# SCH_t4_MFA_LCD_2021-12-15.net
KiCad netlist of a schematic drawn in EasyEDA
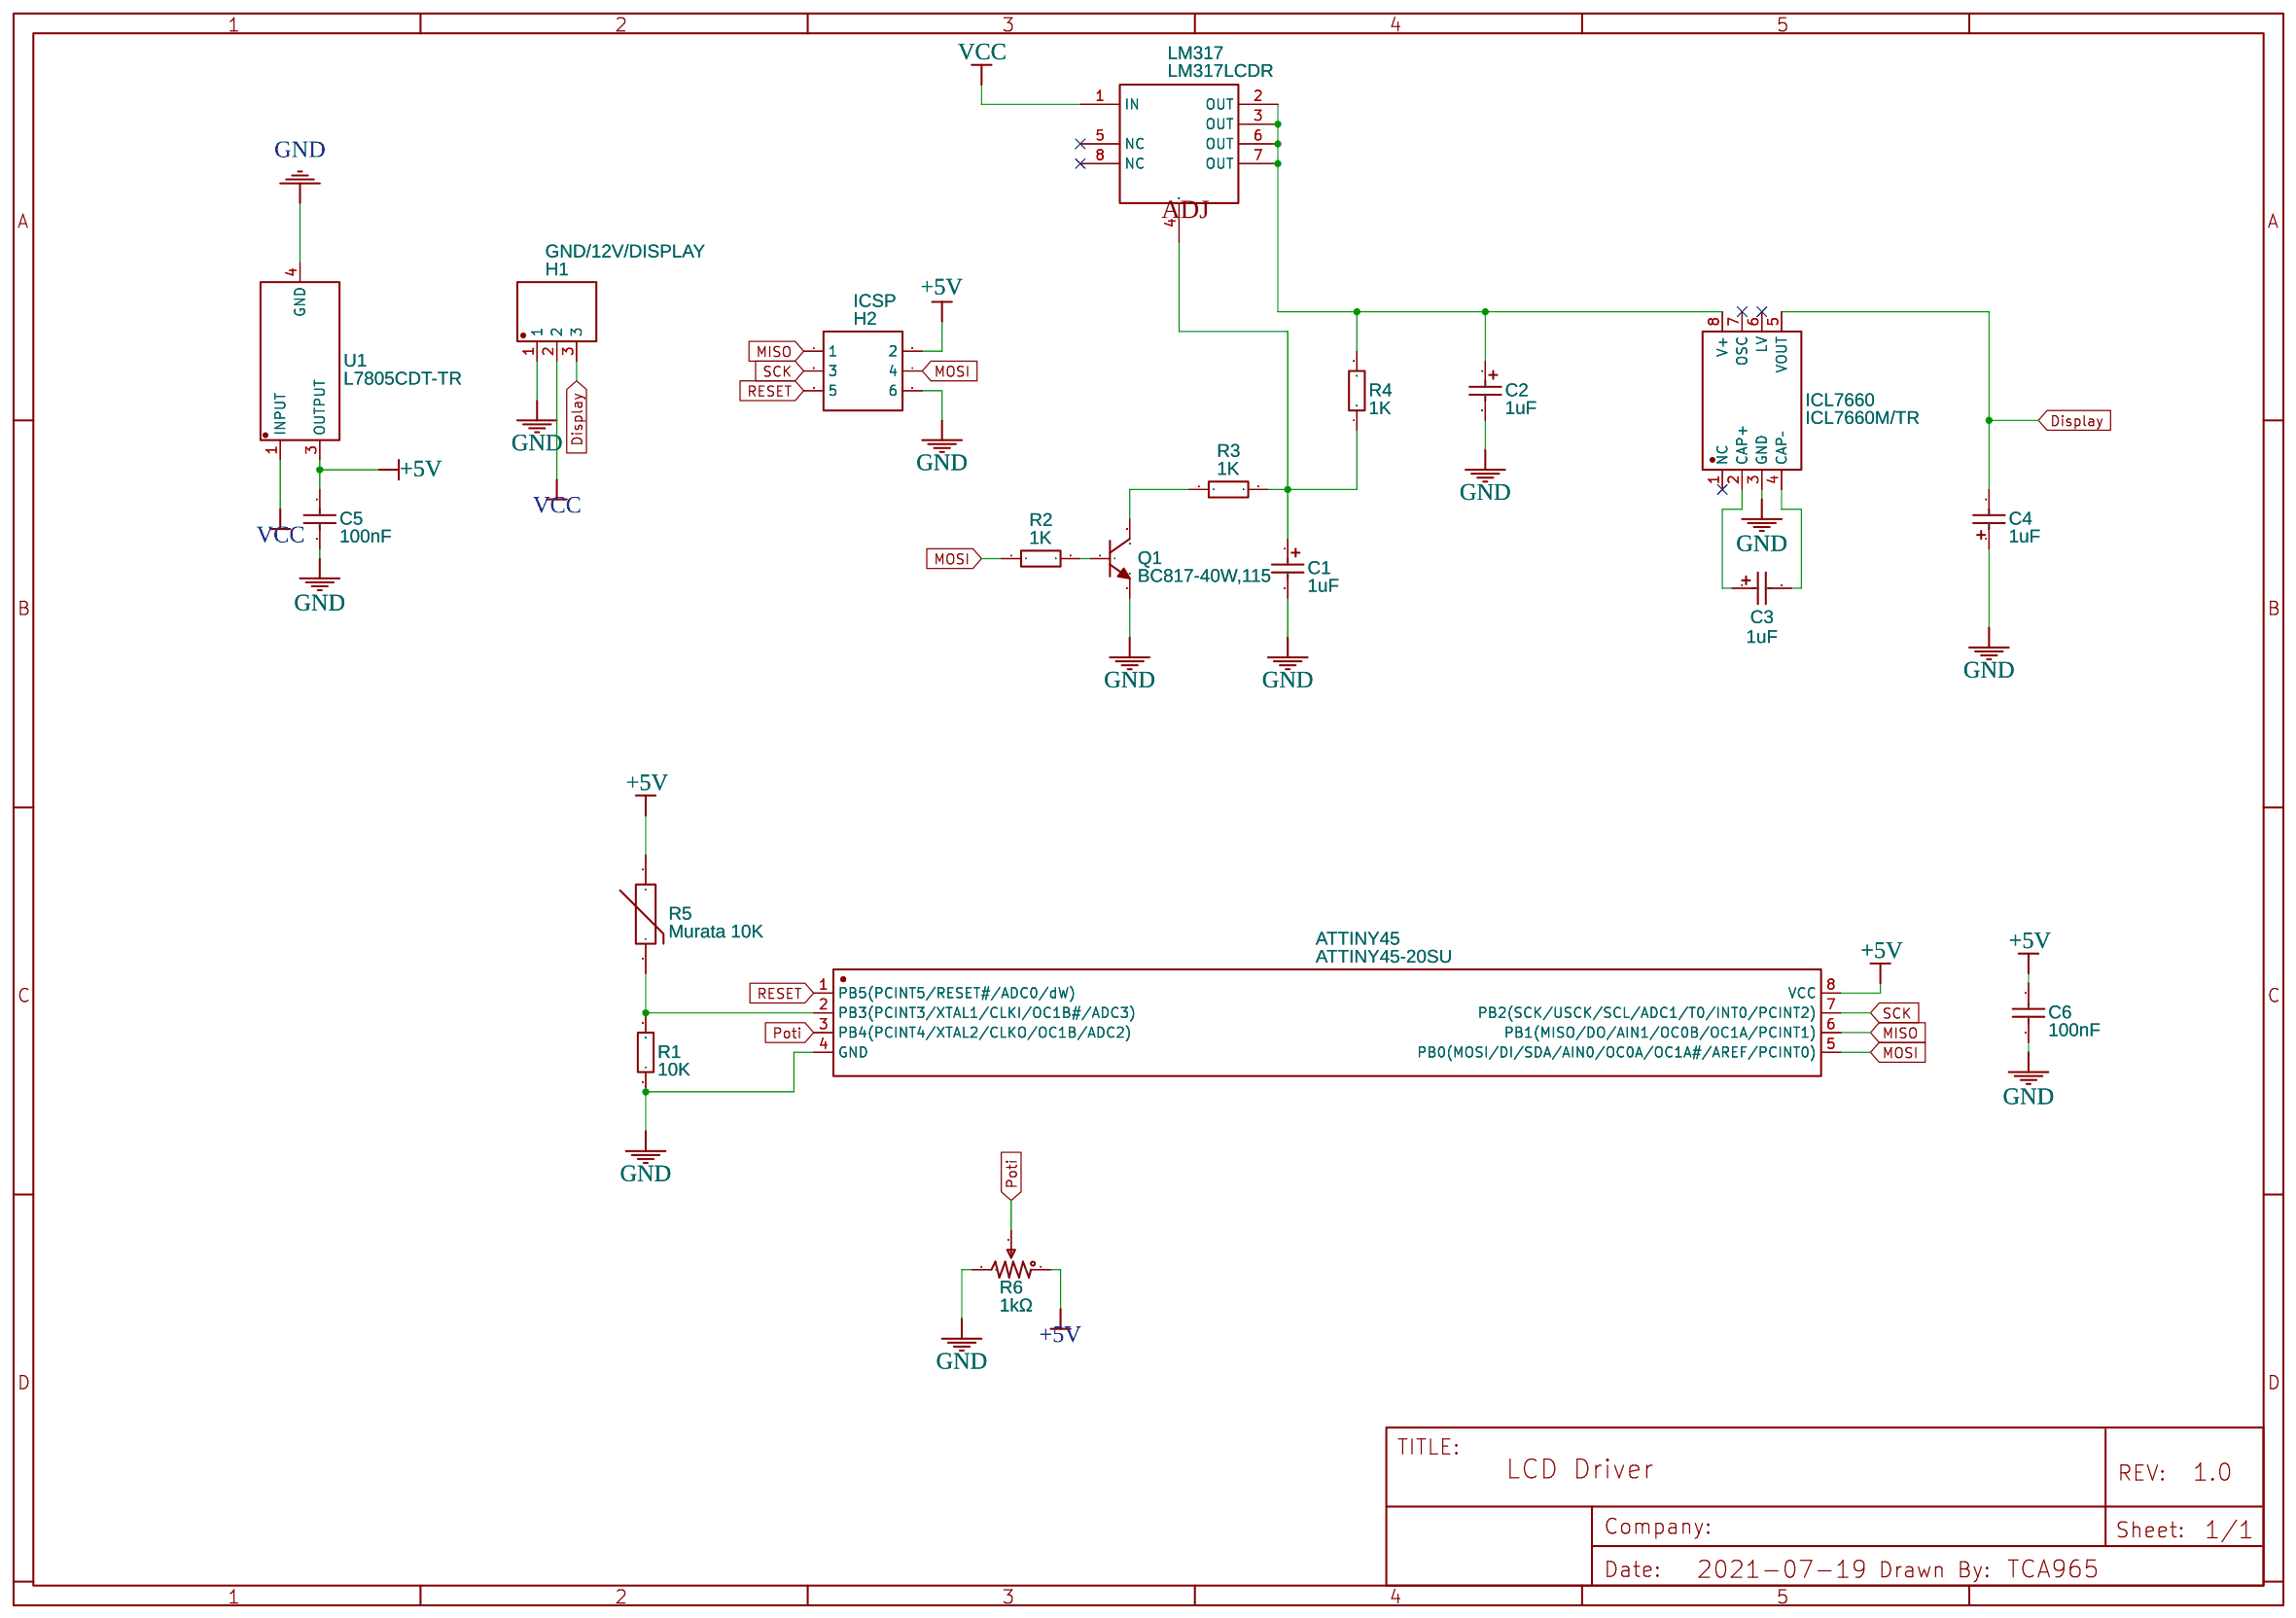
[diagram p0: schematic sheet]

(export (version "E")
  (design (tool "Eeschema 10.0.6"))
  (components
    (comp (ref "ATTINY45")
      (value "ATTINY45-20SU")
      (fields (field (name "BOM_Supplier Part") "C62689"))
      (libsource (lib "") (part "ATTINY45-20SU"))
    )
    (comp (ref "C1")
      (value "1uF")
      (fields
        (field (name "BOM_Manufacturer Part") "293D105X9050C2TE3")
        (field (name "BOM_Supplier Part") "C130371")
      )
      (libsource (lib "") (part "293D105X9050C2TE3_2"))
    )
    (comp (ref "C2")
      (value "1uF")
      (fields
        (field (name "BOM_Manufacturer Part") "293D105X9050C2TE3")
        (field (name "BOM_Supplier Part") "C130371")
      )
      (libsource (lib "") (part "293D105X9050C2TE3_2"))
    )
    (comp (ref "C3")
      (value "1uF")
      (fields
        (field (name "BOM_Manufacturer Part") "293D105X9050C2TE3")
        (field (name "BOM_Supplier Part") "C130371")
      )
      (libsource (lib "") (part "293D105X9050C2TE3_1"))
    )
    (comp (ref "C4")
      (value "1uF")
      (fields
        (field (name "BOM_Manufacturer Part") "293D105X9050C2TE3")
        (field (name "BOM_Supplier Part") "C130371")
      )
      (libsource (lib "") (part "293D105X9050C2TE3"))
    )
    (comp (ref "C5")
      (value "100nF")
      (fields
        (field (name "BOM_Manufacturer Part") "C1206N104J050T")
        (field (name "BOM_Supplier Part") "C105970")
      )
      (libsource (lib "") (part "C1206N104J050T"))
    )
    (comp (ref "C6")
      (value "100nF")
      (fields
        (field (name "BOM_Manufacturer Part") "C1206N104J050T")
        (field (name "BOM_Supplier Part") "C105970")
      )
      (libsource (lib "") (part "C1206N104J050T"))
    )
    (comp (ref "GND/12V/DISPLAY")
      (value "H1")
      (fields
        (field (name "BOM_Manufacturer Part") "210S-1*3P L=11.6MMGold-plated black")
        (field (name "BOM_Supplier Part") "C124376")
      )
      (libsource (lib "") (part "210S-1*3P L=11.6MMGold-plated black"))
    )
    (comp (ref "ICL7660")
      (value "ICL7660M/TR")
      (fields (field (name "BOM_Supplier Part") "C356724"))
      (libsource (lib "") (part "ICL7660M/TR"))
    )
    (comp (ref "ICSP")
      (value "H2")
      (fields
        (field (name "BOM_Manufacturer Part") "Header-Male-2.54_2x3")
        (field (name "BOM_Supplier Part") "C65114")
      )
      (libsource (lib "") (part "Header-Male-2.54_2x3"))
    )
    (comp (ref "LM317")
      (value "LM317LCDR")
      (fields (field (name "BOM_Supplier Part") "C105219"))
      (libsource (lib "") (part "LM317LCDR"))
    )
    (comp (ref "Q1")
      (value "BC817-40W,115")
      (fields (field (name "BOM_Supplier Part") "C75565"))
      (libsource (lib "") (part "BC817-40W,115"))
    )
    (comp (ref "R1")
      (value "10K")
      (fields
        (field (name "BOM_Manufacturer Part") "TR0805B10KP0525")
        (field (name "BOM_Supplier Part") "C188360")
      )
      (libsource (lib "") (part "TR0805B10KP0525"))
    )
    (comp (ref "R2")
      (value "1K")
      (fields
        (field (name "BOM_Manufacturer Part") "0805WAD1001T5E")
        (field (name "BOM_Supplier Part") "C169072")
      )
      (libsource (lib "") (part "0805WAD1001T5E"))
    )
    (comp (ref "R3")
      (value "1K")
      (fields
        (field (name "BOM_Manufacturer Part") "0805WAD1001T5E")
        (field (name "BOM_Supplier Part") "C169072")
      )
      (libsource (lib "") (part "0805WAD1001T5E"))
    )
    (comp (ref "R4")
      (value "1K")
      (fields
        (field (name "BOM_Manufacturer Part") "0805WAD1001T5E")
        (field (name "BOM_Supplier Part") "C169072")
      )
      (libsource (lib "") (part "0805WAD1001T5E_1"))
    )
    (comp (ref "R5")
      (value "Murata 10K")
      (fields
        (field (name "BOM_Manufacturer Part") "NXRT15XH103FA1B030")
        (field (name "BOM_Supplier Part") "C152559")
      )
      (libsource (lib "") (part "NXRT15XH103FA1B030"))
    )
    (comp (ref "R6")
      (value "1kΩ")
      (fields
        (field (name "BOM_Manufacturer Part") "3314G-1-503E")
        (field (name "BOM_Supplier Part") "C719184")
      )
      (libsource (lib "") (part "3314G-1-503E"))
    )
    (comp (ref "U1")
      (value "L7805CDT-TR")
      (fields (field (name "BOM_Supplier Part") "C310413"))
      (libsource (lib "") (part "L7805CDT-TR"))
    )
  )
  (nets
    (net (code "1") (name "+5V") (class "Default")
      (node (ref "ATTINY45") (pin "8") (pinfunction "VCC_8") (pintype "unspecified"))
      (node (ref "C5") (pin "2") (pinfunction "2_2") (pintype "input"))
      (node (ref "C6") (pin "2") (pinfunction "2_2") (pintype "input"))
      (node (ref "ICSP") (pin "2") (pinfunction "2_2") (pintype "input"))
      (node (ref "R5") (pin "2") (pinfunction "2_2") (pintype "unspecified"))
      (node (ref "R6") (pin "1") (pinfunction "1_1") (pintype "unspecified"))
      (node (ref "U1") (pin "3") (pinfunction "OUTPUT_3") (pintype "unspecified"))
    )
    (net (code "2") (name "Display") (class "Default")
      (node (ref "C4") (pin "2") (pinfunction "2_2") (pintype "input"))
      (node (ref "GND/12V/DISPLAY") (pin "3") (pinfunction "3_3") (pintype "unspecified"))
      (node (ref "ICL7660") (pin "5") (pinfunction "VOUT_5") (pintype "unspecified"))
    )
    (net (code "3") (name "GND") (class "Default")
      (node (ref "ATTINY45") (pin "4") (pinfunction "GND_4") (pintype "unspecified"))
      (node (ref "C1") (pin "2") (pinfunction "2_2") (pintype "input"))
      (node (ref "C2") (pin "2") (pinfunction "2_2") (pintype "input"))
      (node (ref "C4") (pin "1") (pinfunction "1_1") (pintype "input"))
      (node (ref "C5") (pin "1") (pinfunction "1_1") (pintype "input"))
      (node (ref "C6") (pin "1") (pinfunction "1_1") (pintype "input"))
      (node (ref "GND/12V/DISPLAY") (pin "1") (pinfunction "1_1") (pintype "unspecified"))
      (node (ref "ICL7660") (pin "3") (pinfunction "GND_3") (pintype "unspecified"))
      (node (ref "ICSP") (pin "6") (pinfunction "6_6") (pintype "input"))
      (node (ref "Q1") (pin "2") (pinfunction "2_2") (pintype "input"))
      (node (ref "R1") (pin "1") (pinfunction "1_1") (pintype "unspecified"))
      (node (ref "R6") (pin "3") (pinfunction "3_3") (pintype "unspecified"))
      (node (ref "U1") (pin "4") (pinfunction "GND_4") (pintype "unspecified"))
    )
    (net (code "4") (name "MISO") (class "Default")
      (node (ref "ATTINY45") (pin "6") (pinfunction "PB1(MISO/DO/AIN1/OC0B/OC1A/PCINT1)_6") (pintype "unspecified"))
      (node (ref "ICSP") (pin "1") (pinfunction "1_1") (pintype "input"))
    )
    (net (code "5") (name "MOSI") (class "Default")
      (node (ref "ATTINY45") (pin "5") (pinfunction "PB0(MOSI/DI/SDA/AIN0/OC0A/OC1A#/AREF/PCINT0)_5") (pintype "unspecified"))
      (node (ref "ICSP") (pin "4") (pinfunction "4_4") (pintype "input"))
      (node (ref "R2") (pin "1") (pinfunction "1_1") (pintype "unspecified"))
    )
    (net (code "6") (name "Net-(ATTINY45-PB3(PCINT3{slash}XTAL1{slash}CLKI{slash}OC1B#{slash}ADC3))") (class "Default")
      (node (ref "ATTINY45") (pin "2") (pinfunction "PB3(PCINT3/XTAL1/CLKI/OC1B#/ADC3)_2") (pintype "unspecified"))
      (node (ref "R1") (pin "2") (pinfunction "2_2") (pintype "unspecified"))
      (node (ref "R5") (pin "1") (pinfunction "1_1") (pintype "unspecified"))
    )
    (net (code "7") (name "Net-(ICL7660-CAP+)") (class "Default")
      (node (ref "C3") (pin "1") (pinfunction "1_1") (pintype "input"))
      (node (ref "ICL7660") (pin "2") (pinfunction "CAP+_2") (pintype "unspecified"))
    )
    (net (code "8") (name "Net-(ICL7660-CAP–)") (class "Default")
      (node (ref "C3") (pin "2") (pinfunction "2_2") (pintype "input"))
      (node (ref "ICL7660") (pin "4") (pinfunction "CAP–_4") (pintype "unspecified"))
    )
    (net (code "9") (name "Net-(ICL7660-V+)") (class "Default")
      (node (ref "C2") (pin "1") (pinfunction "1_1") (pintype "input"))
      (node (ref "ICL7660") (pin "8") (pinfunction "V+_8") (pintype "unspecified"))
      (node (ref "LM317") (pin "2") (pinfunction "OUT_2") (pintype "passive"))
      (node (ref "LM317") (pin "3") (pinfunction "OUT_3") (pintype "passive"))
      (node (ref "LM317") (pin "6") (pinfunction "OUT_6") (pintype "passive"))
      (node (ref "LM317") (pin "7") (pinfunction "OUT_7") (pintype "passive"))
      (node (ref "R4") (pin "2") (pinfunction "2_2") (pintype "unspecified"))
    )
    (net (code "10") (name "Net-(LM317-ADJ)") (class "Default")
      (node (ref "C1") (pin "1") (pinfunction "1_1") (pintype "input"))
      (node (ref "LM317") (pin "4") (pinfunction "ADJ_4") (pintype "unspecified"))
      (node (ref "R3") (pin "2") (pinfunction "2_2") (pintype "unspecified"))
      (node (ref "R4") (pin "1") (pinfunction "1_1") (pintype "unspecified"))
    )
    (net (code "11") (name "Net-(Q1-Pad1)") (class "Default")
      (node (ref "Q1") (pin "1") (pinfunction "1_1") (pintype "input"))
      (node (ref "R2") (pin "2") (pinfunction "2_2") (pintype "unspecified"))
    )
    (net (code "12") (name "Net-(Q1-Pad3)") (class "Default")
      (node (ref "Q1") (pin "3") (pinfunction "3_3") (pintype "input"))
      (node (ref "R3") (pin "1") (pinfunction "1_1") (pintype "unspecified"))
    )
    (net (code "13") (name "Poti") (class "Default")
      (node (ref "ATTINY45") (pin "3") (pinfunction "PB4(PCINT4/XTAL2/CLKO/OC1B/ADC2)_3") (pintype "unspecified"))
      (node (ref "R6") (pin "2") (pinfunction "2_2") (pintype "unspecified"))
    )
    (net (code "14") (name "RESET") (class "Default")
      (node (ref "ATTINY45") (pin "1") (pinfunction "PB5(PCINT5/RESET#/ADC0/dW)_1") (pintype "unspecified"))
      (node (ref "ICSP") (pin "5") (pinfunction "5_5") (pintype "input"))
    )
    (net (code "15") (name "SCK") (class "Default")
      (node (ref "ATTINY45") (pin "7") (pinfunction "PB2(SCK/USCK/SCL/ADC1/T0/INT0/PCINT2)_7") (pintype "unspecified"))
      (node (ref "ICSP") (pin "3") (pinfunction "3_3") (pintype "input"))
    )
    (net (code "16") (name "VCC") (class "Default")
      (node (ref "GND/12V/DISPLAY") (pin "2") (pinfunction "2_2") (pintype "unspecified"))
      (node (ref "LM317") (pin "1") (pinfunction "IN_1") (pintype "passive"))
      (node (ref "U1") (pin "1") (pinfunction "INPUT_1") (pintype "unspecified"))
    )
    (net (code "17") (name "unconnected-(ICL7660-LV-Pad6)") (class "Default")
      (node (ref "ICL7660") (pin "6") (pinfunction "LV_6") (pintype "unspecified+no_connect"))
    )
    (net (code "18") (name "unconnected-(ICL7660-NC-Pad1)") (class "Default")
      (node (ref "ICL7660") (pin "1") (pinfunction "NC_1") (pintype "unspecified+no_connect"))
    )
    (net (code "19") (name "unconnected-(ICL7660-OSC-Pad7)") (class "Default")
      (node (ref "ICL7660") (pin "7") (pinfunction "OSC_7") (pintype "unspecified+no_connect"))
    )
    (net (code "20") (name "unconnected-(LM317-NC-Pad5)") (class "Default")
      (node (ref "LM317") (pin "5") (pinfunction "NC_5") (pintype "unspecified+no_connect"))
    )
    (net (code "21") (name "unconnected-(LM317-NC-Pad8)") (class "Default")
      (node (ref "LM317") (pin "8") (pinfunction "NC_8") (pintype "unspecified+no_connect"))
    )
  )
)
